# Power.net
KiCad netlist of a schematic drawn in Altium Designer
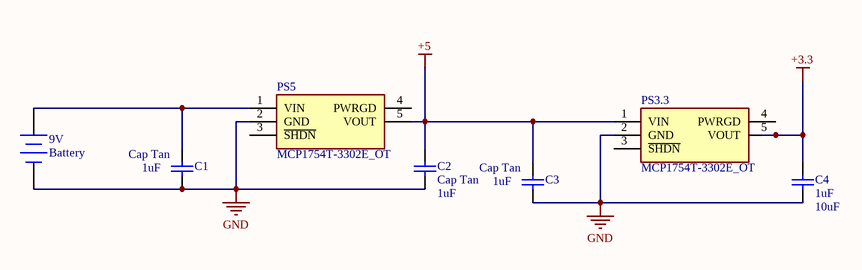
[diagram p0: Power.SchDoc]

(export (version "E")
  (design (tool "Eeschema 10.0.6"))
  (components
    (comp (ref "9V")
      (value "Battery")
      (footprint "BAT-2")
      (description "Multicell Battery")
      (fields (field (name "PUBLISHER") "Altium Limited"))
      (libsource (lib "Miscellaneous Devices") (part "Battery"))
    )
    (comp (ref "C1")
      (value "Cap Tan")
      (footprint "1608[0603]")
      (description "Capacitor (Semiconductor SIM Model)")
      (fields (field (name "ALTIUM_VALUE") "1uF") (field (name "PUBLISHER") "Altium Limited"))
      (libsource (lib "Miscellaneous Devices") (part "Cap Semi"))
    )
    (comp (ref "C2")
      (value "Cap Tan")
      (footprint "1608[0603]")
      (description "Capacitor (Semiconductor SIM Model)")
      (fields (field (name "ALTIUM_VALUE") "1uF") (field (name "PUBLISHER") "Altium Limited"))
      (libsource (lib "Miscellaneous Devices") (part "Cap Semi"))
    )
    (comp (ref "C3")
      (value "Cap Tan")
      (footprint "1608[0603]")
      (description "Capacitor (Semiconductor SIM Model)")
      (fields (field (name "ALTIUM_VALUE") "1uF") (field (name "PUBLISHER") "Altium Limited"))
      (libsource (lib "Miscellaneous Devices") (part "Cap Semi"))
    )
    (comp (ref "C4")
      (value "1uF")
      (footprint "1608[0603]")
      (description "Capacitor (Semiconductor SIM Model)")
      (fields (field (name "ALTIUM_VALUE") "10uF") (field (name "PUBLISHER") "Altium Limited"))
      (libsource (lib "Miscellaneous Devices") (part "Cap Semi"))
    )
    (comp (ref "PS3.3")
      (value "MCP1754T-3302E_OT")
      (footprint "SamacSys:SOT95P270X145-5N")
      (description "Power Supply")
      (fields
        (field (name "MANUFACTURER_PART_NUMBER") "MCP1754T-3302E/OT")
        (field (name "MOUSER PART NUMBER") "579-MCP1754T3302EOT")
      )
      (libsource (lib "*") (part "MCP1754T-3302E_OT"))
    )
    (comp (ref "PS5")
      (value "MCP1754T-3302E_OT")
      (footprint "SamacSys:SOT95P270X145-5N")
      (description "Power Supply")
      (fields
        (field (name "MANUFACTURER_PART_NUMBER") "MCP1754T-3302E/OT")
        (field (name "MOUSER PART NUMBER") "579-MCP1754T3302EOT")
      )
      (libsource (lib "*") (part "MCP1754T-3302E_OT"))
    )
  )
  (nets
    (net (code "1") (name "+3.3") (class "Default")
      (node (ref "C4") (pin "1") (pinfunction "1_1") (pintype "passive"))
      (node (ref "PS3.3") (pin "5") (pinfunction "VOUT_5") (pintype "passive"))
    )
    (net (code "2") (name "+5") (class "Default")
      (node (ref "C2") (pin "1") (pinfunction "1_1") (pintype "passive"))
      (node (ref "C3") (pin "2") (pinfunction "2_2") (pintype "passive"))
      (node (ref "PS3.3") (pin "1") (pinfunction "VIN_1") (pintype "passive"))
      (node (ref "PS5") (pin "5") (pinfunction "VOUT_5") (pintype "passive"))
    )
    (net (code "3") (name "GND") (class "Default")
      (node (ref "9V") (pin "2") (pinfunction "-_2") (pintype "passive"))
      (node (ref "C1") (pin "1") (pinfunction "1_1") (pintype "passive"))
      (node (ref "C2") (pin "2") (pinfunction "2_2") (pintype "passive"))
      (node (ref "C3") (pin "1") (pinfunction "1_1") (pintype "passive"))
      (node (ref "C4") (pin "2") (pinfunction "2_2") (pintype "passive"))
      (node (ref "PS3.3") (pin "2") (pinfunction "GND_2") (pintype "passive"))
      (node (ref "PS5") (pin "2") (pinfunction "GND_2") (pintype "passive"))
    )
    (net (code "4") (name "Net-(9V-+)") (class "Default")
      (node (ref "9V") (pin "1") (pinfunction "+_1") (pintype "passive"))
      (node (ref "C1") (pin "2") (pinfunction "2_2") (pintype "passive"))
      (node (ref "PS5") (pin "1") (pinfunction "VIN_1") (pintype "passive"))
    )
    (net (code "5") (name "unconnected-(PS3.3-PWRGD-Pad4)") (class "Default")
      (node (ref "PS3.3") (pin "4") (pinfunction "PWRGD_4") (pintype "passive"))
    )
    (net (code "6") (name "unconnected-(PS3.3-~{SHDN}-Pad3)") (class "Default")
      (node (ref "PS3.3") (pin "3") (pinfunction "~{SHDN}_3") (pintype "passive"))
    )
    (net (code "7") (name "unconnected-(PS5-PWRGD-Pad4)") (class "Default")
      (node (ref "PS5") (pin "4") (pinfunction "PWRGD_4") (pintype "passive"))
    )
    (net (code "8") (name "unconnected-(PS5-~{SHDN}-Pad3)") (class "Default")
      (node (ref "PS5") (pin "3") (pinfunction "~{SHDN}_3") (pintype "passive"))
    )
  )
)
